# A6_dianshe2_yuanlitu.net
KiCad netlist of a schematic drawn in Altium Designer
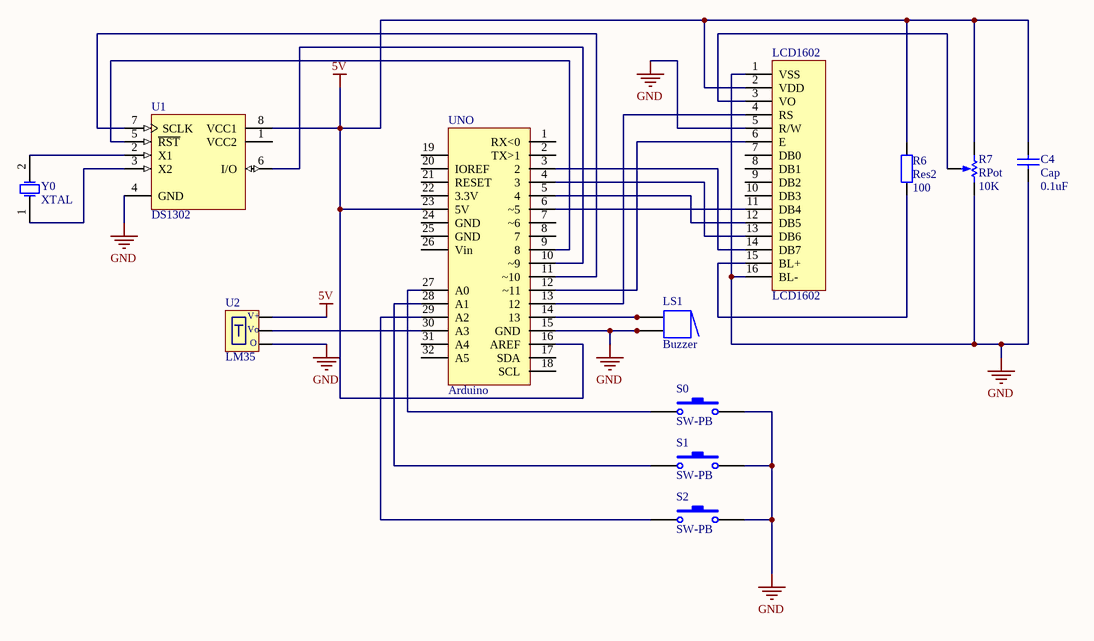
[diagram p0: A6_dianshe2_yuanlitu.SchDoc]

(export (version "E")
  (design (tool "Eeschema 10.0.6"))
  (components
    (comp (ref "C4")
      (value "Cap")
      (footprint "RAD0.2")
      (description "Capacitor")
      (fields (field (name "ALTIUM_VALUE") "0.1uF") (field (name "PUBLISHER") "Altium Limited"))
      (libsource (lib "Miscellaneous Devices") (part "Cap"))
    )
    (comp (ref "LCD1602")
      (value "LCD1602")
      (footprint "LCD1602")
      (description "液晶屏")
      (libsource (lib "LixhSch") (part "LCD1602"))
    )
    (comp (ref "LS1")
      (value "Buzzer")
      (footprint "Buzzer")
      (description "Magnetic Transducer Buzzer")
      (fields (field (name "PUBLISHER") "Altium Limited"))
      (libsource (lib "Miscellaneous Devices") (part "Buzzer"))
    )
    (comp (ref "R6")
      (value "Res2")
      (footprint "AXIAL-0.4")
      (description "Resistor")
      (fields (field (name "ALTIUM_VALUE") "100") (field (name "PUBLISHER") "Altium Limited"))
      (libsource (lib "Miscellaneous Devices") (part "Res2"))
    )
    (comp (ref "R7")
      (value "RPot")
      (footprint "VR5")
      (description "Potentiometer")
      (fields (field (name "ALTIUM_VALUE") "10K") (field (name "PUBLISHER") "Altium Limited"))
      (libsource (lib "Miscellaneous Devices") (part "RPot"))
    )
    (comp (ref "S0")
      (value "SW-PB")
      (footprint "AN-S")
      (description "Switch")
      (fields (field (name "PUBLISHER") "Altium Limited"))
      (libsource (lib "Miscellaneous Devices") (part "SW-PB"))
    )
    (comp (ref "S1")
      (value "SW-PB")
      (footprint "AN-S")
      (description "Switch")
      (fields (field (name "PUBLISHER") "Altium Limited"))
      (libsource (lib "Miscellaneous Devices") (part "SW-PB"))
    )
    (comp (ref "S2")
      (value "SW-PB")
      (footprint "AN-S")
      (description "Switch")
      (fields (field (name "PUBLISHER") "Altium Limited"))
      (libsource (lib "Miscellaneous Devices") (part "SW-PB"))
    )
    (comp (ref "U1")
      (value "DS1302")
      (footprint "DIP8")
      (description "Trickle Charge Timekeeping Chip")
      (fields (field (name "PUBLISHER") "Altium Limited"))
      (libsource (lib "Dallas Peripheral Real Time Clock") (part "DS1302"))
    )
    (comp (ref "U2")
      (value "LM35")
      (footprint "LM35")
      (description "LM35温度传感器")
      (libsource (lib "LixhSch") (part "LM35"))
    )
    (comp (ref "UNO")
      (value "Arduino")
      (footprint "Arduino-UNO")
      (libsource (lib "LixhSch") (part "Arduino-UNO"))
    )
    (comp (ref "Y0")
      (value "XTAL")
      (footprint "R38")
      (description "Crystal Oscillator")
      (fields (field (name "PUBLISHER") "Altium Limited"))
      (libsource (lib "Miscellaneous Devices") (part "XTAL"))
    )
  )
  (nets
    (net (code "1") (name "5V") (class "Default")
      (node (ref "C4") (pin "2") (pinfunction "2_2") (pintype "passive"))
      (node (ref "LCD1602") (pin "2") (pinfunction "VDD_2") (pintype "power_in"))
      (node (ref "R6") (pin "2") (pinfunction "2_2") (pintype "passive"))
      (node (ref "R7") (pin "1") (pinfunction "TOP_1") (pintype "passive"))
      (node (ref "U1") (pin "8") (pinfunction "VCC1_8") (pintype "power_in"))
      (node (ref "U2") (pin "1") (pinfunction "1_1") (pintype "power_in"))
      (node (ref "UNO") (pin "16") (pinfunction "AREF_16") (pintype "power_in"))
      (node (ref "UNO") (pin "23") (pinfunction "5V_23") (pintype "power_in"))
    )
    (net (code "2") (name "GND") (class "Default")
      (node (ref "C4") (pin "1") (pinfunction "1_1") (pintype "passive"))
      (node (ref "LCD1602") (pin "1") (pinfunction "VSS_1") (pintype "power_in"))
      (node (ref "LCD1602") (pin "16") (pinfunction "BL-_16") (pintype "power_in"))
      (node (ref "LCD1602") (pin "5") (pinfunction "R/W_5") (pintype "power_in"))
      (node (ref "LS1") (pin "2") (pinfunction "2_2") (pintype "passive"))
      (node (ref "LS1") (pin "2A") (pinfunction "2A_2A") (pintype "passive"))
      (node (ref "R7") (pin "3") (pinfunction "BOT_3") (pintype "passive"))
      (node (ref "S0") (pin "2") (pinfunction "2_2") (pintype "passive"))
      (node (ref "S1") (pin "2") (pinfunction "2_2") (pintype "passive"))
      (node (ref "S2") (pin "2") (pinfunction "2_2") (pintype "passive"))
      (node (ref "U1") (pin "4") (pinfunction "GND_4") (pintype "power_in"))
      (node (ref "U2") (pin "3") (pinfunction "3_3") (pintype "power_in"))
      (node (ref "UNO") (pin "15") (pinfunction "GND_15") (pintype "power_in"))
    )
    (net (code "3") (name "Net-(LCD1602-BL+)") (class "Default")
      (node (ref "LCD1602") (pin "15") (pinfunction "BL+_15") (pintype "power_in"))
      (node (ref "R6") (pin "1") (pinfunction "1_1") (pintype "passive"))
    )
    (net (code "4") (name "Net-(LCD1602-DB4)") (class "Default")
      (node (ref "LCD1602") (pin "11") (pinfunction "DB4_11") (pintype "power_in"))
      (node (ref "UNO") (pin "6") (pinfunction "~5_6") (pintype "power_in"))
    )
    (net (code "5") (name "Net-(LCD1602-DB5)") (class "Default")
      (node (ref "LCD1602") (pin "12") (pinfunction "DB5_12") (pintype "power_in"))
      (node (ref "UNO") (pin "5") (pinfunction "4_5") (pintype "power_in"))
    )
    (net (code "6") (name "Net-(LCD1602-DB6)") (class "Default")
      (node (ref "LCD1602") (pin "13") (pinfunction "DB6_13") (pintype "power_in"))
      (node (ref "UNO") (pin "4") (pinfunction "3_4") (pintype "power_in"))
    )
    (net (code "7") (name "Net-(LCD1602-DB7)") (class "Default")
      (node (ref "LCD1602") (pin "14") (pinfunction "DB7_14") (pintype "power_in"))
      (node (ref "UNO") (pin "3") (pinfunction "2_3") (pintype "power_in"))
    )
    (net (code "8") (name "Net-(LCD1602-E)") (class "Default")
      (node (ref "LCD1602") (pin "6") (pinfunction "E_6") (pintype "power_in"))
      (node (ref "UNO") (pin "12") (pinfunction "~11_12") (pintype "power_in"))
    )
    (net (code "9") (name "Net-(LCD1602-RS)") (class "Default")
      (node (ref "LCD1602") (pin "4") (pinfunction "RS_4") (pintype "power_in"))
      (node (ref "UNO") (pin "13") (pinfunction "12_13") (pintype "power_in"))
    )
    (net (code "10") (name "Net-(LCD1602-VO)") (class "Default")
      (node (ref "LCD1602") (pin "3") (pinfunction "VO_3") (pintype "power_in"))
      (node (ref "R7") (pin "2") (pinfunction "TAP_2") (pintype "passive"))
    )
    (net (code "11") (name "Net-(U1-I{slash}O)") (class "Default")
      (node (ref "U1") (pin "6") (pinfunction "I/O_6") (pintype "bidirectional"))
      (node (ref "UNO") (pin "10") (pinfunction "~9_10") (pintype "power_in"))
    )
    (net (code "12") (name "Net-(U1-SCLK)") (class "Default")
      (node (ref "U1") (pin "7") (pinfunction "SCLK_7") (pintype "input"))
      (node (ref "UNO") (pin "11") (pinfunction "~10_11") (pintype "power_in"))
    )
    (net (code "13") (name "Net-(U1-X1)") (class "Default")
      (node (ref "U1") (pin "2") (pinfunction "X1_2") (pintype "input"))
      (node (ref "Y0") (pin "2") (pinfunction "OSC2_2") (pintype "passive"))
    )
    (net (code "14") (name "Net-(U1-X2)") (class "Default")
      (node (ref "U1") (pin "3") (pinfunction "X2_3") (pintype "input"))
      (node (ref "Y0") (pin "1") (pinfunction "OSC1_1") (pintype "passive"))
    )
    (net (code "15") (name "Net-(U1-~{RST})") (class "Default")
      (node (ref "U1") (pin "5") (pinfunction "~{RST}_5") (pintype "input"))
      (node (ref "UNO") (pin "9") (pinfunction "8_9") (pintype "power_in"))
    )
    (net (code "16") (name "Net-(UNO-13)") (class "Default")
      (node (ref "LS1") (pin "1") (pinfunction "1_1") (pintype "passive"))
      (node (ref "LS1") (pin "1A") (pinfunction "1A_1A") (pintype "passive"))
      (node (ref "UNO") (pin "14") (pinfunction "13_14") (pintype "power_in"))
    )
    (net (code "17") (name "Net-(UNO-A0)") (class "Default")
      (node (ref "S0") (pin "1") (pinfunction "1_1") (pintype "passive"))
      (node (ref "UNO") (pin "27") (pinfunction "A0_27") (pintype "power_in"))
    )
    (net (code "18") (name "Net-(UNO-A1)") (class "Default")
      (node (ref "S1") (pin "1") (pinfunction "1_1") (pintype "passive"))
      (node (ref "UNO") (pin "28") (pinfunction "A1_28") (pintype "power_in"))
    )
    (net (code "19") (name "Net-(UNO-A2)") (class "Default")
      (node (ref "S2") (pin "1") (pinfunction "1_1") (pintype "passive"))
      (node (ref "UNO") (pin "29") (pinfunction "A2_29") (pintype "power_in"))
    )
    (net (code "20") (name "Net-(UNO-A3)") (class "Default")
      (node (ref "U2") (pin "2") (pinfunction "2_2") (pintype "passive"))
      (node (ref "UNO") (pin "30") (pinfunction "A3_30") (pintype "power_in"))
    )
    (net (code "21") (name "unconnected-(LCD1602-DB0-Pad7)") (class "Default")
      (node (ref "LCD1602") (pin "7") (pinfunction "DB0_7") (pintype "power_in"))
    )
    (net (code "22") (name "unconnected-(LCD1602-DB1-Pad8)") (class "Default")
      (node (ref "LCD1602") (pin "8") (pinfunction "DB1_8") (pintype "power_in"))
    )
    (net (code "23") (name "unconnected-(LCD1602-DB2-Pad9)") (class "Default")
      (node (ref "LCD1602") (pin "9") (pinfunction "DB2_9") (pintype "power_in"))
    )
    (net (code "24") (name "unconnected-(LCD1602-DB3-Pad10)") (class "Default")
      (node (ref "LCD1602") (pin "10") (pinfunction "DB3_10") (pintype "power_in"))
    )
    (net (code "25") (name "unconnected-(U1-VCC2-Pad1)") (class "Default")
      (node (ref "U1") (pin "1") (pinfunction "VCC2_1") (pintype "power_in"))
    )
    (net (code "26") (name "unconnected-(UNO-3.3V-Pad22)") (class "Default")
      (node (ref "UNO") (pin "22") (pinfunction "3.3V_22") (pintype "power_in"))
    )
    (net (code "27") (name "unconnected-(UNO-7-Pad8)") (class "Default")
      (node (ref "UNO") (pin "8") (pinfunction "7_8") (pintype "power_in"))
    )
    (net (code "28") (name "unconnected-(UNO-A4-Pad31)") (class "Default")
      (node (ref "UNO") (pin "31") (pinfunction "A4_31") (pintype "power_in"))
    )
    (net (code "29") (name "unconnected-(UNO-A5-Pad32)") (class "Default")
      (node (ref "UNO") (pin "32") (pinfunction "A5_32") (pintype "power_in"))
    )
    (net (code "30") (name "unconnected-(UNO-GND-Pad24)") (class "Default")
      (node (ref "UNO") (pin "24") (pinfunction "GND_24") (pintype "power_in"))
    )
    (net (code "31") (name "unconnected-(UNO-GND-Pad25)") (class "Default")
      (node (ref "UNO") (pin "25") (pinfunction "GND_25") (pintype "power_in"))
    )
    (net (code "32") (name "unconnected-(UNO-IOREF-Pad20)") (class "Default")
      (node (ref "UNO") (pin "20") (pinfunction "IOREF_20") (pintype "power_in"))
    )
    (net (code "33") (name "unconnected-(UNO-Pad19)") (class "Default")
      (node (ref "UNO") (pin "19") (pintype "power_in"))
    )
    (net (code "34") (name "unconnected-(UNO-RESET-Pad21)") (class "Default")
      (node (ref "UNO") (pin "21") (pinfunction "RESET_21") (pintype "power_in"))
    )
    (net (code "35") (name "unconnected-(UNO-RX<0-Pad1)") (class "Default")
      (node (ref "UNO") (pin "1") (pinfunction "RX<0_1") (pintype "power_in"))
    )
    (net (code "36") (name "unconnected-(UNO-SCL-Pad18)") (class "Default")
      (node (ref "UNO") (pin "18") (pinfunction "SCL_18") (pintype "power_in"))
    )
    (net (code "37") (name "unconnected-(UNO-SDA-Pad17)") (class "Default")
      (node (ref "UNO") (pin "17") (pinfunction "SDA_17") (pintype "power_in"))
    )
    (net (code "38") (name "unconnected-(UNO-TX>1-Pad2)") (class "Default")
      (node (ref "UNO") (pin "2") (pinfunction "TX>1_2") (pintype "power_in"))
    )
    (net (code "39") (name "unconnected-(UNO-Vin-Pad26)") (class "Default")
      (node (ref "UNO") (pin "26") (pinfunction "Vin_26") (pintype "power_in"))
    )
    (net (code "40") (name "unconnected-(UNO-~6-Pad7)") (class "Default")
      (node (ref "UNO") (pin "7") (pinfunction "~6_7") (pintype "power_in"))
    )
  )
)
